# weather_box.net
KiCad netlist of a schematic drawn in EAGLE
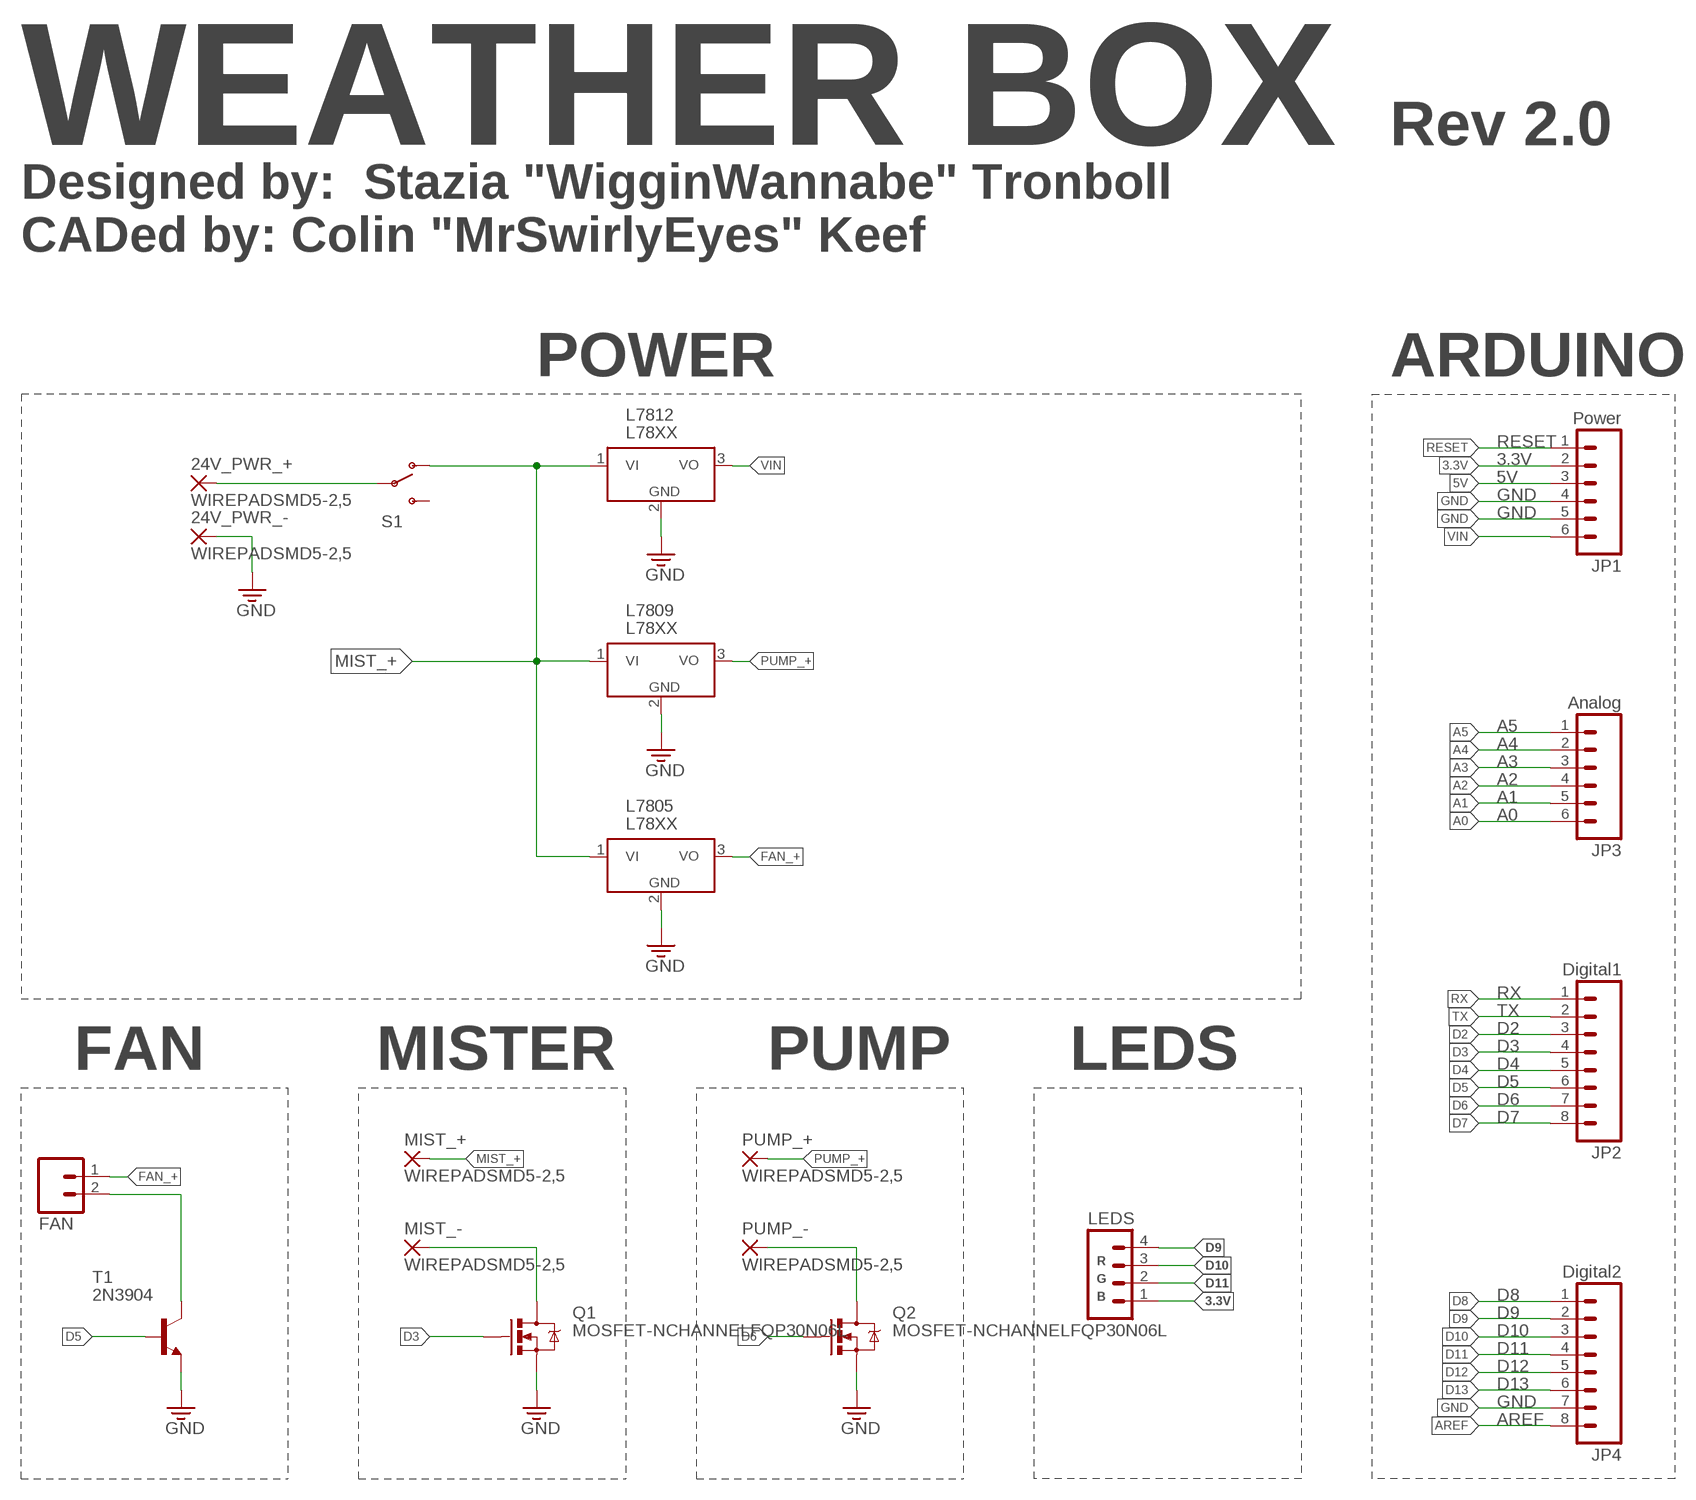
[diagram p0: schematic, sheet 1]

(export (version "E")
  (design (tool "Eeschema 10.0.6"))
  (components
    (comp (ref "24V_PWR_+")
      (value "WIREPADSMD5-2,5")
      (footprint "eagle-import:5-2,5")
      (libsource (lib "eagle-import") (part "WIREPADSMD5-2,5"))
    )
    (comp (ref "24V_PWR_-")
      (value "WIREPADSMD5-2,5")
      (footprint "eagle-import:5-2,5")
      (libsource (lib "eagle-import") (part "WIREPADSMD5-2,5"))
    )
    (comp (ref "FAN")
      (value "M02PTH")
      (footprint "eagle-import:1X02")
      (libsource (lib "eagle-import") (part "M02PTH"))
    )
    (comp (ref "JP1")
      (value "Power")
      (footprint "eagle-import:1X06")
      (libsource (lib "eagle-import") (part "M06SIP"))
    )
    (comp (ref "JP2")
      (value "Digital1")
      (footprint "eagle-import:1X08")
      (libsource (lib "eagle-import") (part "M08"))
    )
    (comp (ref "JP3")
      (value "Analog")
      (footprint "eagle-import:1X06")
      (libsource (lib "eagle-import") (part "M06SIP"))
    )
    (comp (ref "JP4")
      (value "Digital2")
      (footprint "eagle-import:1X08")
      (libsource (lib "eagle-import") (part "M08"))
    )
    (comp (ref "L7805")
      (value "L78XX")
      (footprint "eagle-import:TO-220-HEATSINK")
      (libsource (lib "eagle-import") (part "L78XX"))
    )
    (comp (ref "L7809")
      (value "L78XX")
      (footprint "eagle-import:TO-220-HEATSINK")
      (libsource (lib "eagle-import") (part "L78XX"))
    )
    (comp (ref "L7812")
      (value "L78XX")
      (footprint "eagle-import:TO-220-HEATSINK")
      (libsource (lib "eagle-import") (part "L78XX"))
    )
    (comp (ref "LEDS")
      (value "M04PTH")
      (footprint "eagle-import:1X04")
      (libsource (lib "eagle-import") (part "M04PTH"))
    )
    (comp (ref "MIST_+")
      (value "WIREPADSMD5-2,5")
      (footprint "eagle-import:5-2,5")
      (libsource (lib "eagle-import") (part "WIREPADSMD5-2,5"))
    )
    (comp (ref "MIST_-")
      (value "WIREPADSMD5-2,5")
      (footprint "eagle-import:5-2,5")
      (libsource (lib "eagle-import") (part "WIREPADSMD5-2,5"))
    )
    (comp (ref "PUMP_+")
      (value "WIREPADSMD5-2,5")
      (footprint "eagle-import:5-2,5")
      (libsource (lib "eagle-import") (part "WIREPADSMD5-2,5"))
    )
    (comp (ref "PUMP_-")
      (value "WIREPADSMD5-2,5")
      (footprint "eagle-import:5-2,5")
      (libsource (lib "eagle-import") (part "WIREPADSMD5-2,5"))
    )
    (comp (ref "Q1")
      (value "MOSFET-NCHANNELFQP30N06L")
      (footprint "eagle-import:TO220V")
      (libsource (lib "eagle-import") (part "MOSFET-NCHANNELFQP30N06L"))
    )
    (comp (ref "Q2")
      (value "MOSFET-NCHANNELFQP30N06L")
      (footprint "eagle-import:TO220V")
      (libsource (lib "eagle-import") (part "MOSFET-NCHANNELFQP30N06L"))
    )
    (comp (ref "S1")
      (value "SWITCH-SPDTPTH")
      (footprint "eagle-import:SWITCH-SPDT")
      (libsource (lib "eagle-import") (part "SWITCH-SPDTPTH"))
    )
    (comp (ref "T1")
      (value "2N3904")
      (footprint "eagle-import:TO92")
      (libsource (lib "eagle-import") (part "2N3904"))
    )
  )
  (nets
    (net (code "1") (name "3.3V") (class "Default")
      (node (ref "JP1") (pin "2") (pinfunction "2_2") (pintype "passive"))
      (node (ref "LEDS") (pin "1") (pinfunction "1_1") (pintype "passive"))
    )
    (net (code "2") (name "5V") (class "Default")
      (node (ref "JP1") (pin "3") (pinfunction "3_3") (pintype "passive"))
    )
    (net (code "3") (name "A0") (class "Default")
      (node (ref "JP3") (pin "6") (pinfunction "6_6") (pintype "passive"))
    )
    (net (code "4") (name "A1") (class "Default")
      (node (ref "JP3") (pin "5") (pinfunction "5_5") (pintype "passive"))
    )
    (net (code "5") (name "A2") (class "Default")
      (node (ref "JP3") (pin "4") (pinfunction "4_4") (pintype "passive"))
    )
    (net (code "6") (name "A3") (class "Default")
      (node (ref "JP3") (pin "3") (pinfunction "3_3") (pintype "passive"))
    )
    (net (code "7") (name "A4") (class "Default")
      (node (ref "JP3") (pin "2") (pinfunction "2_2") (pintype "passive"))
    )
    (net (code "8") (name "A5") (class "Default")
      (node (ref "JP3") (pin "1") (pinfunction "1_1") (pintype "passive"))
    )
    (net (code "9") (name "AREF") (class "Default")
      (node (ref "JP4") (pin "8") (pinfunction "8_8") (pintype "passive"))
    )
    (net (code "10") (name "D2") (class "Default")
      (node (ref "JP2") (pin "3") (pinfunction "3_3") (pintype "passive"))
    )
    (net (code "11") (name "D3") (class "Default")
      (node (ref "JP2") (pin "4") (pinfunction "4_4") (pintype "passive"))
      (node (ref "Q1") (pin "1") (pinfunction "G_1") (pintype "passive"))
    )
    (net (code "12") (name "D4") (class "Default")
      (node (ref "JP2") (pin "5") (pinfunction "5_5") (pintype "passive"))
    )
    (net (code "13") (name "D5") (class "Default")
      (node (ref "JP2") (pin "6") (pinfunction "6_6") (pintype "passive"))
      (node (ref "T1") (pin "2") (pinfunction "B_2") (pintype "passive"))
    )
    (net (code "14") (name "D6") (class "Default")
      (node (ref "JP2") (pin "7") (pinfunction "7_7") (pintype "passive"))
      (node (ref "Q2") (pin "1") (pinfunction "G_1") (pintype "passive"))
    )
    (net (code "15") (name "D7") (class "Default")
      (node (ref "JP2") (pin "8") (pinfunction "8_8") (pintype "passive"))
    )
    (net (code "16") (name "D8") (class "Default")
      (node (ref "JP4") (pin "1") (pinfunction "1_1") (pintype "passive"))
    )
    (net (code "17") (name "D9") (class "Default")
      (node (ref "JP4") (pin "2") (pinfunction "2_2") (pintype "passive"))
      (node (ref "LEDS") (pin "4") (pinfunction "4_4") (pintype "passive"))
    )
    (net (code "18") (name "D10") (class "Default")
      (node (ref "JP4") (pin "3") (pinfunction "3_3") (pintype "passive"))
      (node (ref "LEDS") (pin "3") (pinfunction "3_3") (pintype "passive"))
    )
    (net (code "19") (name "D11") (class "Default")
      (node (ref "JP4") (pin "4") (pinfunction "4_4") (pintype "passive"))
      (node (ref "LEDS") (pin "2") (pinfunction "2_2") (pintype "passive"))
    )
    (net (code "20") (name "D12") (class "Default")
      (node (ref "JP4") (pin "5") (pinfunction "5_5") (pintype "passive"))
    )
    (net (code "21") (name "D13") (class "Default")
      (node (ref "JP4") (pin "6") (pinfunction "6_6") (pintype "passive"))
    )
    (net (code "22") (name "FAN_+") (class "Default")
      (node (ref "FAN") (pin "1") (pinfunction "1_1") (pintype "passive"))
      (node (ref "L7805") (pin "3") (pinfunction "VO_3") (pintype "bidirectional"))
    )
    (net (code "23") (name "GND") (class "Default")
      (node (ref "24V_PWR_-") (pin "1") (pinfunction "P_1") (pintype "passive"))
      (node (ref "JP1") (pin "4") (pinfunction "4_4") (pintype "passive"))
      (node (ref "JP1") (pin "5") (pinfunction "5_5") (pintype "passive"))
      (node (ref "JP4") (pin "7") (pinfunction "7_7") (pintype "passive"))
      (node (ref "L7805") (pin "2") (pinfunction "GND_2") (pintype "bidirectional"))
      (node (ref "L7809") (pin "2") (pinfunction "GND_2") (pintype "bidirectional"))
      (node (ref "L7812") (pin "2") (pinfunction "GND_2") (pintype "bidirectional"))
      (node (ref "Q1") (pin "3") (pinfunction "S_3") (pintype "passive"))
      (node (ref "Q2") (pin "3") (pinfunction "S_3") (pintype "passive"))
      (node (ref "T1") (pin "3") (pinfunction "E_3") (pintype "passive"))
    )
    (net (code "24") (name "MIST_+") (class "Default")
      (node (ref "L7805") (pin "1") (pinfunction "VI_1") (pintype "bidirectional"))
      (node (ref "L7809") (pin "1") (pinfunction "VI_1") (pintype "bidirectional"))
      (node (ref "L7812") (pin "1") (pinfunction "VI_1") (pintype "bidirectional"))
      (node (ref "MIST_+") (pin "1") (pinfunction "P_1") (pintype "passive"))
      (node (ref "S1") (pin "1") (pinfunction "O_1") (pintype "passive"))
    )
    (net (code "25") (name "Net-(24V_PWR_+-P)") (class "Default")
      (node (ref "24V_PWR_+") (pin "1") (pinfunction "P_1") (pintype "passive"))
      (node (ref "S1") (pin "2") (pinfunction "P_2") (pintype "passive"))
    )
    (net (code "26") (name "Net-(MIST_--P)") (class "Default")
      (node (ref "MIST_-") (pin "1") (pinfunction "P_1") (pintype "passive"))
      (node (ref "Q1") (pin "2") (pinfunction "D_2") (pintype "passive"))
    )
    (net (code "27") (name "Net-(PUMP_--P)") (class "Default")
      (node (ref "PUMP_-") (pin "1") (pinfunction "P_1") (pintype "passive"))
      (node (ref "Q2") (pin "2") (pinfunction "D_2") (pintype "passive"))
    )
    (net (code "28") (name "Net-(T1-C)") (class "Default")
      (node (ref "FAN") (pin "2") (pinfunction "2_2") (pintype "passive"))
      (node (ref "T1") (pin "1") (pinfunction "C_1") (pintype "passive"))
    )
    (net (code "29") (name "PUMP_+") (class "Default")
      (node (ref "L7809") (pin "3") (pinfunction "VO_3") (pintype "bidirectional"))
      (node (ref "PUMP_+") (pin "1") (pinfunction "P_1") (pintype "passive"))
    )
    (net (code "30") (name "RESET") (class "Default")
      (node (ref "JP1") (pin "1") (pinfunction "1_1") (pintype "passive"))
    )
    (net (code "31") (name "RX") (class "Default")
      (node (ref "JP2") (pin "1") (pinfunction "1_1") (pintype "passive"))
    )
    (net (code "32") (name "TX") (class "Default")
      (node (ref "JP2") (pin "2") (pinfunction "2_2") (pintype "passive"))
    )
    (net (code "33") (name "VIN") (class "Default")
      (node (ref "JP1") (pin "6") (pinfunction "6_6") (pintype "passive"))
      (node (ref "L7812") (pin "3") (pinfunction "VO_3") (pintype "bidirectional"))
    )
    (net (code "34") (name "unconnected-(S1-S-Pad3)") (class "Default")
      (node (ref "S1") (pin "3") (pinfunction "S_3") (pintype "passive"))
    )
  )
)
